# LC_LPF9.net
KiCad netlist of a schematic drawn in Altium Designer
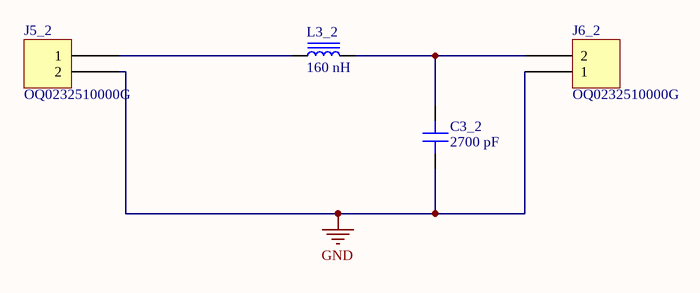
[diagram p0: LC_LPF9.SchDoc]

(export (version "E")
  (design (tool "Eeschema 10.0.6"))
  (components
    (comp (ref "C3_2")
      (value "2700 pF")
      (footprint "CAP 0603_1608")
      (description "CAP CER 2700PF 25V NP0 0603")
      (fields (field (name "PART NUMBER") "C0603C272F3GAC7867") (field (name "MANUFACTURER") "KEMET"))
      (libsource (lib "Celestial Altium Library - altium_library") (part "Capacitor"))
    )
    (comp (ref "J5_2")
      (value "OQ0232510000G")
      (footprint "FCI 06-381-2PIN")
      (description "TERM BLOCK HDR 2POS 90DEG 3.81MM")
      (fields (field (name "MANUFACTURER") "Amphenol Anytek"))
      (libsource (lib "") (part "2 Pin_1"))
    )
    (comp (ref "J6_2")
      (value "OQ0232510000G")
      (footprint "FCI 06-381-2PIN")
      (description "TERM BLOCK HDR 2POS 90DEG 3.81MM")
      (fields (field (name "MANUFACTURER") "Amphenol Anytek"))
      (libsource (lib "Celestial Altium Library - altium_library") (part "2 Pin"))
    )
    (comp (ref "L3_2")
      (value "160 nH")
      (footprint "IND 0402_1005 RF WW")
      (description "FIXED IND 160NH 480MA 330MOHM SM")
      (fields
        (field (name "PART NUMBER") "LQW15CNR16J00D")
        (field (name "MANUFACTURER") "Murata Electronics")
      )
      (libsource (lib "Celestial Altium Library - altium_library") (part "Inductor"))
    )
  )
  (nets
    (net (code "1") (name "GND") (class "Default")
      (node (ref "C3_2") (pin "1") (pinfunction "1_1") (pintype "passive"))
      (node (ref "J5_2") (pin "2") (pinfunction "2_2") (pintype "passive"))
      (node (ref "J6_2") (pin "1") (pinfunction "1_1") (pintype "passive"))
    )
    (net (code "2") (name "Net-(C3_2-Pad2)") (class "Default")
      (node (ref "C3_2") (pin "2") (pinfunction "2_2") (pintype "passive"))
      (node (ref "J6_2") (pin "2") (pinfunction "2_2") (pintype "passive"))
      (node (ref "L3_2") (pin "2") (pinfunction "2_2") (pintype "passive"))
    )
    (net (code "3") (name "Net-(J5_2-Pad1)") (class "Default")
      (node (ref "J5_2") (pin "1") (pinfunction "1_1") (pintype "passive"))
      (node (ref "L3_2") (pin "1") (pinfunction "1_1") (pintype "passive"))
    )
  )
)
